# sch_AGV_Input.net
KiCad netlist of a schematic drawn in Altium Designer
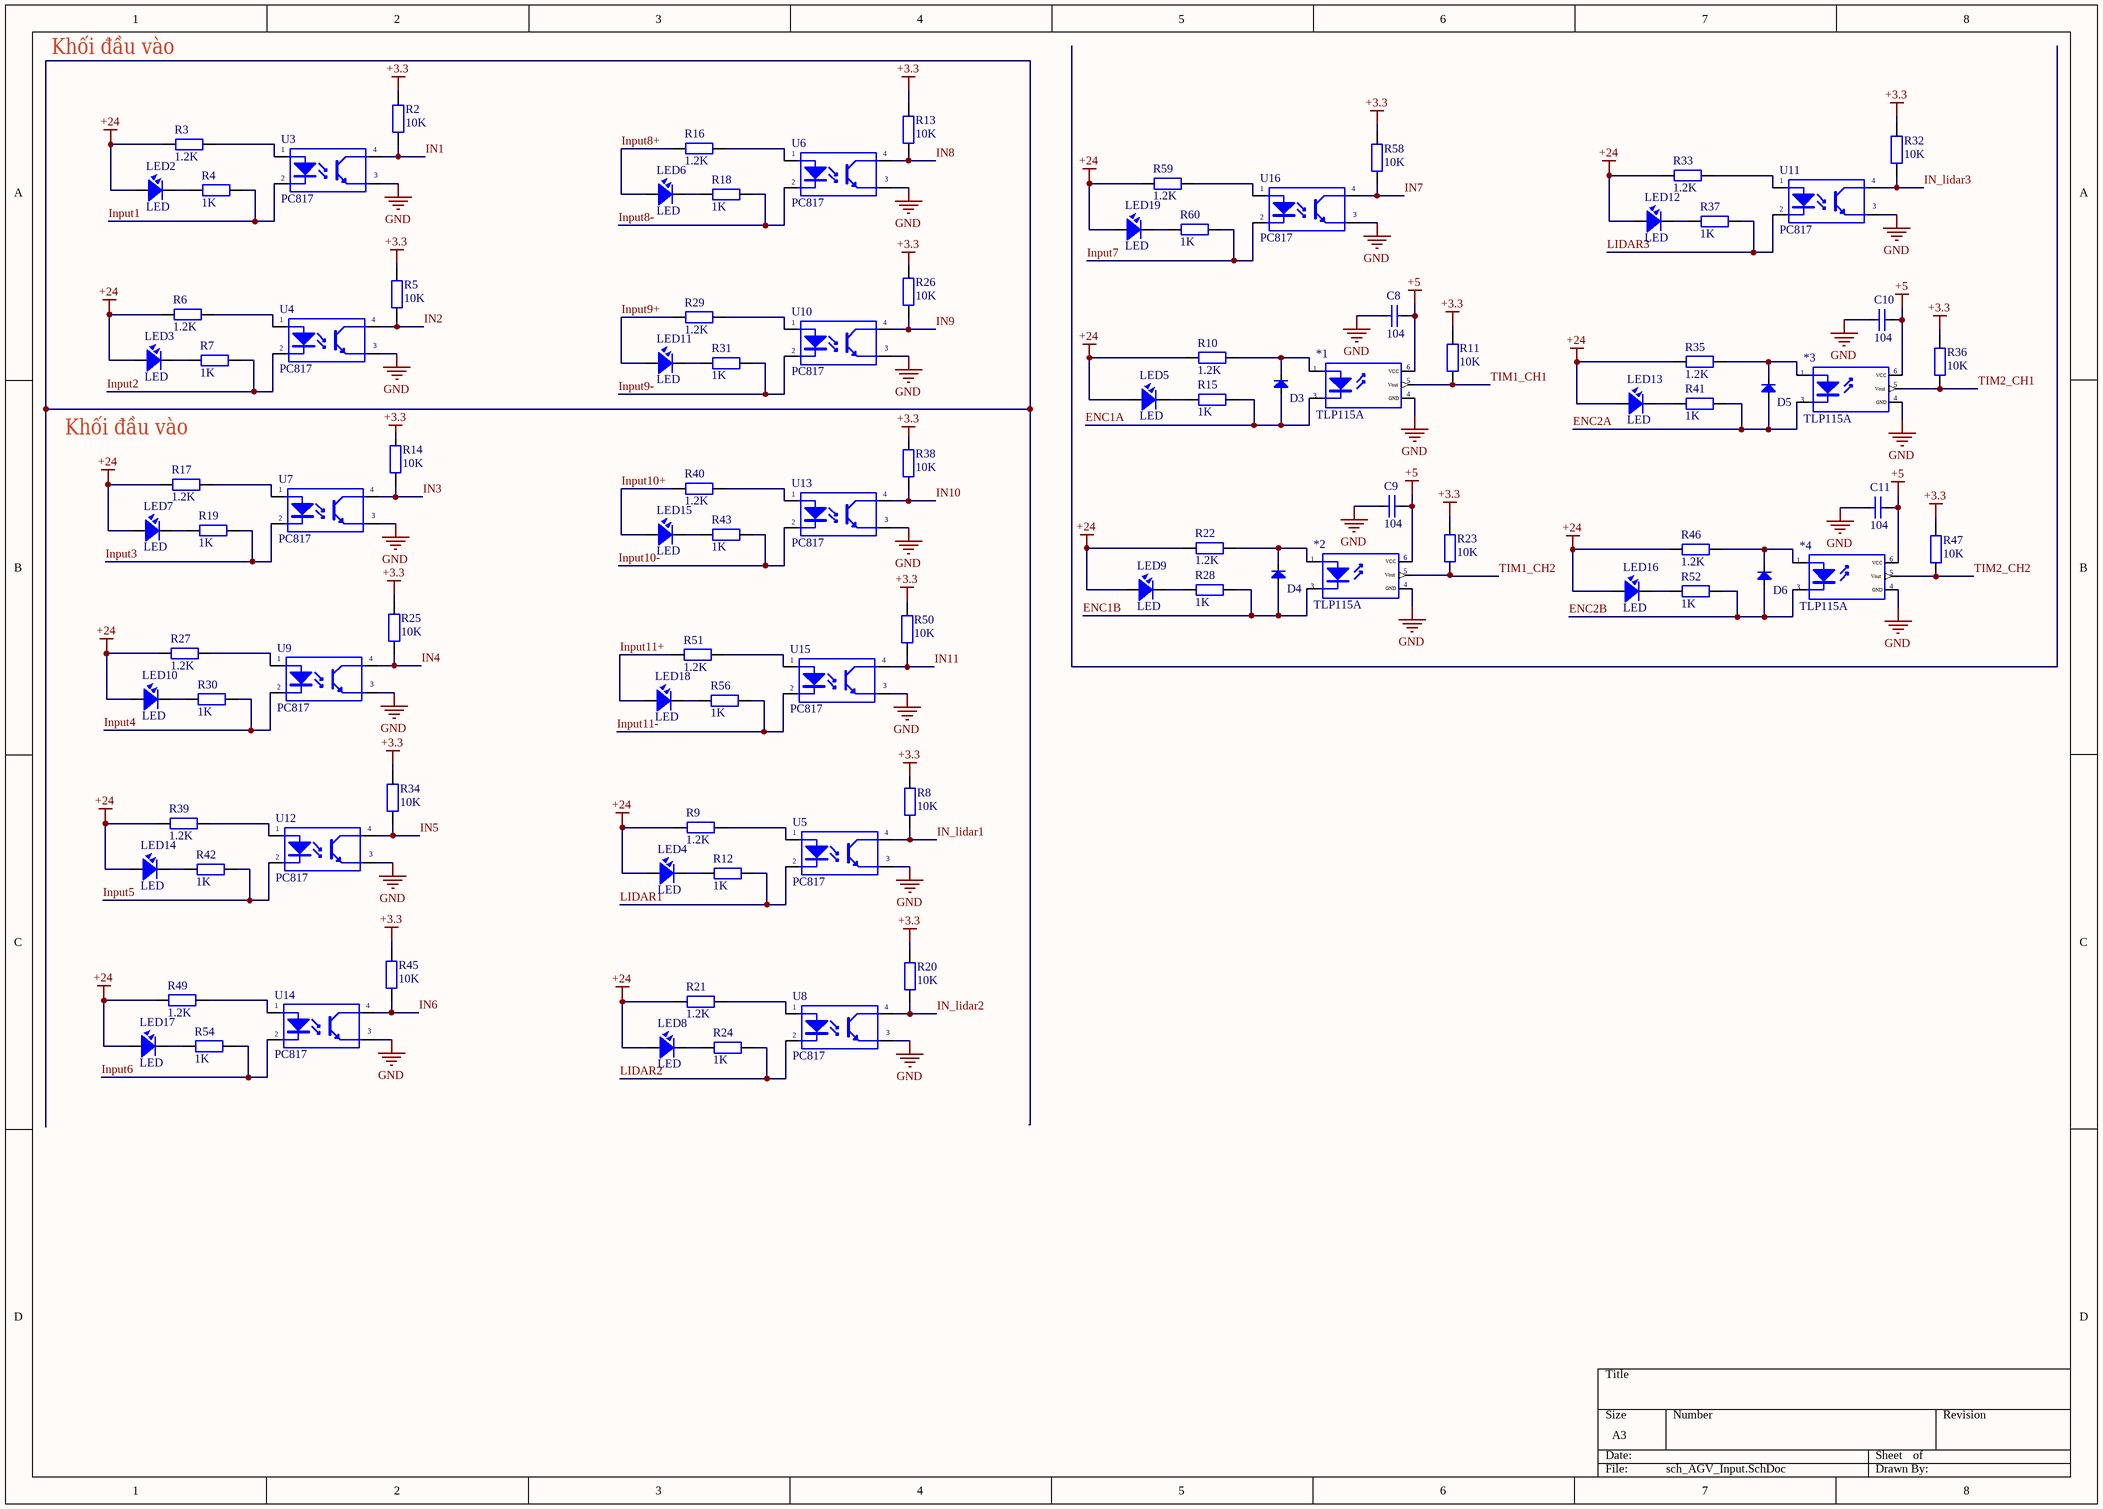
[diagram p0: sch_AGV_Input.SchDoc]

(export (version "E")
  (design (tool "Eeschema 10.0.6"))
  (components
    (comp (ref "*1")
      (value "TLP115A")
      (footprint "SOP5")
      (description "Photocouple")
      (libsource (lib "schelib_AGVcontrol") (part "TLP115A"))
    )
    (comp (ref "*2")
      (value "TLP115A")
      (footprint "SOP5")
      (description "Photocouple")
      (libsource (lib "schelib_AGVcontrol") (part "TLP115A"))
    )
    (comp (ref "*3")
      (value "TLP115A")
      (footprint "SOP5")
      (description "Photocouple")
      (libsource (lib "schelib_AGVcontrol") (part "TLP115A"))
    )
    (comp (ref "*4")
      (value "TLP115A")
      (footprint "SOP5")
      (description "Photocouple")
      (libsource (lib "schelib_AGVcontrol") (part "TLP115A"))
    )
    (comp (ref "C8")
      (value "104")
      (footprint "CAP_0805")
      (description "Capacitor")
      (fields (field (name "PUBLISHER") "Altium Limited"))
      (libsource (lib "schelib_AGVcontrol") (part "CapSMD"))
    )
    (comp (ref "C9")
      (value "104")
      (footprint "CAP_0805")
      (description "Capacitor")
      (fields (field (name "PUBLISHER") "Altium Limited"))
      (libsource (lib "schelib_AGVcontrol") (part "CapSMD"))
    )
    (comp (ref "C10")
      (value "104")
      (footprint "CAP_0805")
      (description "Capacitor")
      (fields (field (name "PUBLISHER") "Altium Limited"))
      (libsource (lib "schelib_AGVcontrol") (part "CapSMD"))
    )
    (comp (ref "C11")
      (value "104")
      (footprint "CAP_0805")
      (description "Capacitor")
      (fields (field (name "PUBLISHER") "Altium Limited"))
      (libsource (lib "schelib_AGVcontrol") (part "CapSMD"))
    )
    (comp (ref "D3")
      (value "Diode")
      (footprint "DIO-214AC(SMA)")
      (description "Default Diode")
      (fields (field (name "PUBLISHER") "Altium Limited"))
      (libsource (lib "schelib_AGVcontrol") (part "Diode"))
    )
    (comp (ref "D4")
      (value "Diode")
      (footprint "DIO-214AC(SMA)")
      (description "Default Diode")
      (fields (field (name "PUBLISHER") "Altium Limited"))
      (libsource (lib "schelib_AGVcontrol") (part "Diode"))
    )
    (comp (ref "D5")
      (value "Diode")
      (footprint "DIO-214AC(SMA)")
      (description "Default Diode")
      (fields (field (name "PUBLISHER") "Altium Limited"))
      (libsource (lib "schelib_AGVcontrol") (part "Diode"))
    )
    (comp (ref "D6")
      (value "Diode")
      (footprint "DIO-214AC(SMA)")
      (description "Default Diode")
      (fields (field (name "PUBLISHER") "Altium Limited"))
      (libsource (lib "schelib_AGVcontrol") (part "Diode"))
    )
    (comp (ref "LED2")
      (value "LED")
      (footprint "LED_BLUE_SMD_0805")
      (description "LED Single colour Green and Red")
      (libsource (lib "schelib_AGVcontrol") (part "LED"))
    )
    (comp (ref "LED3")
      (value "LED")
      (footprint "LED_BLUE_SMD_0805")
      (description "LED Single colour Green and Red")
      (libsource (lib "schelib_AGVcontrol") (part "LED"))
    )
    (comp (ref "LED4")
      (value "LED")
      (footprint "LED_BLUE_SMD_0805")
      (description "LED Single colour Green and Red")
      (libsource (lib "schelib_AGVcontrol") (part "LED"))
    )
    (comp (ref "LED5")
      (value "LED")
      (footprint "LED_BLUE_SMD_0805")
      (description "LED Single colour Green and Red")
      (libsource (lib "schelib_AGVcontrol") (part "LED"))
    )
    (comp (ref "LED6")
      (value "LED")
      (footprint "LED_BLUE_SMD_0805")
      (description "LED Single colour Green and Red")
      (libsource (lib "schelib_AGVcontrol") (part "LED"))
    )
    (comp (ref "LED7")
      (value "LED")
      (footprint "LED_BLUE_SMD_0805")
      (description "LED Single colour Green and Red")
      (libsource (lib "schelib_AGVcontrol") (part "LED"))
    )
    (comp (ref "LED8")
      (value "LED")
      (footprint "LED_BLUE_SMD_0805")
      (description "LED Single colour Green and Red")
      (libsource (lib "schelib_AGVcontrol") (part "LED"))
    )
    (comp (ref "LED9")
      (value "LED")
      (footprint "LED_BLUE_SMD_0805")
      (description "LED Single colour Green and Red")
      (libsource (lib "schelib_AGVcontrol") (part "LED"))
    )
    (comp (ref "LED10")
      (value "LED")
      (footprint "LED_BLUE_SMD_0805")
      (description "LED Single colour Green and Red")
      (libsource (lib "schelib_AGVcontrol") (part "LED"))
    )
    (comp (ref "LED11")
      (value "LED")
      (footprint "LED_BLUE_SMD_0805")
      (description "LED Single colour Green and Red")
      (libsource (lib "schelib_AGVcontrol") (part "LED"))
    )
    (comp (ref "LED12")
      (value "LED")
      (footprint "LED_BLUE_SMD_0805")
      (description "LED Single colour Green and Red")
      (libsource (lib "schelib_AGVcontrol") (part "LED"))
    )
    (comp (ref "LED13")
      (value "LED")
      (footprint "LED_BLUE_SMD_0805")
      (description "LED Single colour Green and Red")
      (libsource (lib "schelib_AGVcontrol") (part "LED"))
    )
    (comp (ref "LED14")
      (value "LED")
      (footprint "LED_BLUE_SMD_0805")
      (description "LED Single colour Green and Red")
      (libsource (lib "schelib_AGVcontrol") (part "LED"))
    )
    (comp (ref "LED15")
      (value "LED")
      (footprint "LED_BLUE_SMD_0805")
      (description "LED Single colour Green and Red")
      (libsource (lib "schelib_AGVcontrol") (part "LED"))
    )
    (comp (ref "LED16")
      (value "LED")
      (footprint "LED_BLUE_SMD_0805")
      (description "LED Single colour Green and Red")
      (libsource (lib "schelib_AGVcontrol") (part "LED"))
    )
    (comp (ref "LED17")
      (value "LED")
      (footprint "LED_BLUE_SMD_0805")
      (description "LED Single colour Green and Red")
      (libsource (lib "schelib_AGVcontrol") (part "LED"))
    )
    (comp (ref "LED18")
      (value "LED")
      (footprint "LED_BLUE_SMD_0805")
      (description "LED Single colour Green and Red")
      (libsource (lib "schelib_AGVcontrol") (part "LED"))
    )
    (comp (ref "LED19")
      (value "LED")
      (footprint "LED_BLUE_SMD_0805")
      (description "LED Single colour Green and Red")
      (libsource (lib "schelib_AGVcontrol") (part "LED"))
    )
    (comp (ref "R2")
      (value "10K")
      (footprint "RES_SMD_0805")
      (description "Resistor")
      (fields
        (field (name "MANUFACTURER") "Generic Components")
        (field (name "PUBLISHER") "Altium Hobart Technology Centre")
      )
      (libsource (lib "schelib_AGVcontrol") (part "Res"))
    )
    (comp (ref "R3")
      (value "1.2K")
      (footprint "RES_SMD_0805")
      (description "Resistor")
      (fields
        (field (name "MANUFACTURER") "Generic Components")
        (field (name "PUBLISHER") "Altium Hobart Technology Centre")
      )
      (libsource (lib "schelib_AGVcontrol") (part "Res"))
    )
    (comp (ref "R4")
      (value "1K")
      (footprint "RES_SMD_0805")
      (description "Resistor")
      (fields
        (field (name "MANUFACTURER") "Generic Components")
        (field (name "PUBLISHER") "Altium Hobart Technology Centre")
      )
      (libsource (lib "schelib_AGVcontrol") (part "Res"))
    )
    (comp (ref "R5")
      (value "10K")
      (footprint "RES_SMD_0805")
      (description "Resistor")
      (fields
        (field (name "MANUFACTURER") "Generic Components")
        (field (name "PUBLISHER") "Altium Hobart Technology Centre")
      )
      (libsource (lib "schelib_AGVcontrol") (part "Res"))
    )
    (comp (ref "R6")
      (value "1.2K")
      (footprint "RES_SMD_0805")
      (description "Resistor")
      (fields
        (field (name "MANUFACTURER") "Generic Components")
        (field (name "PUBLISHER") "Altium Hobart Technology Centre")
      )
      (libsource (lib "schelib_AGVcontrol") (part "Res"))
    )
    (comp (ref "R7")
      (value "1K")
      (footprint "RES_SMD_0805")
      (description "Resistor")
      (fields
        (field (name "MANUFACTURER") "Generic Components")
        (field (name "PUBLISHER") "Altium Hobart Technology Centre")
      )
      (libsource (lib "schelib_AGVcontrol") (part "Res"))
    )
    (comp (ref "R8")
      (value "10K")
      (footprint "RES_SMD_0805")
      (description "Resistor")
      (fields
        (field (name "MANUFACTURER") "Generic Components")
        (field (name "PUBLISHER") "Altium Hobart Technology Centre")
      )
      (libsource (lib "schelib_AGVcontrol") (part "Res"))
    )
    (comp (ref "R9")
      (value "1.2K")
      (footprint "RES_SMD_0805")
      (description "Resistor")
      (fields
        (field (name "MANUFACTURER") "Generic Components")
        (field (name "PUBLISHER") "Altium Hobart Technology Centre")
      )
      (libsource (lib "schelib_AGVcontrol") (part "Res"))
    )
    (comp (ref "R10")
      (value "1.2K")
      (footprint "RES_SMD_0805")
      (description "Resistor")
      (fields
        (field (name "MANUFACTURER") "Generic Components")
        (field (name "PUBLISHER") "Altium Hobart Technology Centre")
      )
      (libsource (lib "schelib_AGVcontrol") (part "Res"))
    )
    (comp (ref "R11")
      (value "10K")
      (footprint "RES_SMD_0805")
      (description "Resistor")
      (fields
        (field (name "MANUFACTURER") "Generic Components")
        (field (name "PUBLISHER") "Altium Hobart Technology Centre")
      )
      (libsource (lib "schelib_AGVcontrol") (part "Res"))
    )
    (comp (ref "R12")
      (value "1K")
      (footprint "RES_SMD_0805")
      (description "Resistor")
      (fields
        (field (name "MANUFACTURER") "Generic Components")
        (field (name "PUBLISHER") "Altium Hobart Technology Centre")
      )
      (libsource (lib "schelib_AGVcontrol") (part "Res"))
    )
    (comp (ref "R13")
      (value "10K")
      (footprint "RES_SMD_0805")
      (description "Resistor")
      (fields
        (field (name "MANUFACTURER") "Generic Components")
        (field (name "PUBLISHER") "Altium Hobart Technology Centre")
      )
      (libsource (lib "schelib_AGVcontrol") (part "Res"))
    )
    (comp (ref "R14")
      (value "10K")
      (footprint "RES_SMD_0805")
      (description "Resistor")
      (fields
        (field (name "MANUFACTURER") "Generic Components")
        (field (name "PUBLISHER") "Altium Hobart Technology Centre")
      )
      (libsource (lib "schelib_AGVcontrol") (part "Res"))
    )
    (comp (ref "R15")
      (value "1K")
      (footprint "RES_SMD_0805")
      (description "Resistor")
      (fields
        (field (name "MANUFACTURER") "Generic Components")
        (field (name "PUBLISHER") "Altium Hobart Technology Centre")
      )
      (libsource (lib "schelib_AGVcontrol") (part "Res"))
    )
    (comp (ref "R16")
      (value "1.2K")
      (footprint "RES_SMD_0805")
      (description "Resistor")
      (fields
        (field (name "MANUFACTURER") "Generic Components")
        (field (name "PUBLISHER") "Altium Hobart Technology Centre")
      )
      (libsource (lib "schelib_AGVcontrol") (part "Res"))
    )
    (comp (ref "R17")
      (value "1.2K")
      (footprint "RES_SMD_0805")
      (description "Resistor")
      (fields
        (field (name "MANUFACTURER") "Generic Components")
        (field (name "PUBLISHER") "Altium Hobart Technology Centre")
      )
      (libsource (lib "schelib_AGVcontrol") (part "Res"))
    )
    (comp (ref "R18")
      (value "1K")
      (footprint "RES_SMD_0805")
      (description "Resistor")
      (fields
        (field (name "MANUFACTURER") "Generic Components")
        (field (name "PUBLISHER") "Altium Hobart Technology Centre")
      )
      (libsource (lib "schelib_AGVcontrol") (part "Res"))
    )
    (comp (ref "R19")
      (value "1K")
      (footprint "RES_SMD_0805")
      (description "Resistor")
      (fields
        (field (name "MANUFACTURER") "Generic Components")
        (field (name "PUBLISHER") "Altium Hobart Technology Centre")
      )
      (libsource (lib "schelib_AGVcontrol") (part "Res"))
    )
    (comp (ref "R20")
      (value "10K")
      (footprint "RES_SMD_0805")
      (description "Resistor")
      (fields
        (field (name "MANUFACTURER") "Generic Components")
        (field (name "PUBLISHER") "Altium Hobart Technology Centre")
      )
      (libsource (lib "schelib_AGVcontrol") (part "Res"))
    )
    (comp (ref "R21")
      (value "1.2K")
      (footprint "RES_SMD_0805")
      (description "Resistor")
      (fields
        (field (name "MANUFACTURER") "Generic Components")
        (field (name "PUBLISHER") "Altium Hobart Technology Centre")
      )
      (libsource (lib "schelib_AGVcontrol") (part "Res"))
    )
    (comp (ref "R22")
      (value "1.2K")
      (footprint "RES_SMD_0805")
      (description "Resistor")
      (fields
        (field (name "MANUFACTURER") "Generic Components")
        (field (name "PUBLISHER") "Altium Hobart Technology Centre")
      )
      (libsource (lib "schelib_AGVcontrol") (part "Res"))
    )
    (comp (ref "R23")
      (value "10K")
      (footprint "RES_SMD_0805")
      (description "Resistor")
      (fields
        (field (name "MANUFACTURER") "Generic Components")
        (field (name "PUBLISHER") "Altium Hobart Technology Centre")
      )
      (libsource (lib "schelib_AGVcontrol") (part "Res"))
    )
    (comp (ref "R24")
      (value "1K")
      (footprint "RES_SMD_0805")
      (description "Resistor")
      (fields
        (field (name "MANUFACTURER") "Generic Components")
        (field (name "PUBLISHER") "Altium Hobart Technology Centre")
      )
      (libsource (lib "schelib_AGVcontrol") (part "Res"))
    )
    (comp (ref "R25")
      (value "10K")
      (footprint "RES_SMD_0805")
      (description "Resistor")
      (fields
        (field (name "MANUFACTURER") "Generic Components")
        (field (name "PUBLISHER") "Altium Hobart Technology Centre")
      )
      (libsource (lib "schelib_AGVcontrol") (part "Res"))
    )
    (comp (ref "R26")
      (value "10K")
      (footprint "RES_SMD_0805")
      (description "Resistor")
      (fields
        (field (name "MANUFACTURER") "Generic Components")
        (field (name "PUBLISHER") "Altium Hobart Technology Centre")
      )
      (libsource (lib "schelib_AGVcontrol") (part "Res"))
    )
    (comp (ref "R27")
      (value "1.2K")
      (footprint "RES_SMD_0805")
      (description "Resistor")
      (fields
        (field (name "MANUFACTURER") "Generic Components")
        (field (name "PUBLISHER") "Altium Hobart Technology Centre")
      )
      (libsource (lib "schelib_AGVcontrol") (part "Res"))
    )
    (comp (ref "R28")
      (value "1K")
      (footprint "RES_SMD_0805")
      (description "Resistor")
      (fields
        (field (name "MANUFACTURER") "Generic Components")
        (field (name "PUBLISHER") "Altium Hobart Technology Centre")
      )
      (libsource (lib "schelib_AGVcontrol") (part "Res"))
    )
    (comp (ref "R29")
      (value "1.2K")
      (footprint "RES_SMD_0805")
      (description "Resistor")
      (fields
        (field (name "MANUFACTURER") "Generic Components")
        (field (name "PUBLISHER") "Altium Hobart Technology Centre")
      )
      (libsource (lib "schelib_AGVcontrol") (part "Res"))
    )
    (comp (ref "R30")
      (value "1K")
      (footprint "RES_SMD_0805")
      (description "Resistor")
      (fields
        (field (name "MANUFACTURER") "Generic Components")
        (field (name "PUBLISHER") "Altium Hobart Technology Centre")
      )
      (libsource (lib "schelib_AGVcontrol") (part "Res"))
    )
    (comp (ref "R31")
      (value "1K")
      (footprint "RES_SMD_0805")
      (description "Resistor")
      (fields
        (field (name "MANUFACTURER") "Generic Components")
        (field (name "PUBLISHER") "Altium Hobart Technology Centre")
      )
      (libsource (lib "schelib_AGVcontrol") (part "Res"))
    )
    (comp (ref "R32")
      (value "10K")
      (footprint "RES_SMD_0805")
      (description "Resistor")
      (fields
        (field (name "MANUFACTURER") "Generic Components")
        (field (name "PUBLISHER") "Altium Hobart Technology Centre")
      )
      (libsource (lib "schelib_AGVcontrol") (part "Res"))
    )
    (comp (ref "R33")
      (value "1.2K")
      (footprint "RES_SMD_0805")
      (description "Resistor")
      (fields
        (field (name "MANUFACTURER") "Generic Components")
        (field (name "PUBLISHER") "Altium Hobart Technology Centre")
      )
      (libsource (lib "schelib_AGVcontrol") (part "Res"))
    )
    (comp (ref "R34")
      (value "10K")
      (footprint "RES_SMD_0805")
      (description "Resistor")
      (fields
        (field (name "MANUFACTURER") "Generic Components")
        (field (name "PUBLISHER") "Altium Hobart Technology Centre")
      )
      (libsource (lib "schelib_AGVcontrol") (part "Res"))
    )
    (comp (ref "R35")
      (value "1.2K")
      (footprint "RES_SMD_0805")
      (description "Resistor")
      (fields
        (field (name "MANUFACTURER") "Generic Components")
        (field (name "PUBLISHER") "Altium Hobart Technology Centre")
      )
      (libsource (lib "schelib_AGVcontrol") (part "Res"))
    )
    (comp (ref "R36")
      (value "10K")
      (footprint "RES_SMD_0805")
      (description "Resistor")
      (fields
        (field (name "MANUFACTURER") "Generic Components")
        (field (name "PUBLISHER") "Altium Hobart Technology Centre")
      )
      (libsource (lib "schelib_AGVcontrol") (part "Res"))
    )
    (comp (ref "R37")
      (value "1K")
      (footprint "RES_SMD_0805")
      (description "Resistor")
      (fields
        (field (name "MANUFACTURER") "Generic Components")
        (field (name "PUBLISHER") "Altium Hobart Technology Centre")
      )
      (libsource (lib "schelib_AGVcontrol") (part "Res"))
    )
    (comp (ref "R38")
      (value "10K")
      (footprint "RES_SMD_0805")
      (description "Resistor")
      (fields
        (field (name "MANUFACTURER") "Generic Components")
        (field (name "PUBLISHER") "Altium Hobart Technology Centre")
      )
      (libsource (lib "schelib_AGVcontrol") (part "Res"))
    )
    (comp (ref "R39")
      (value "1.2K")
      (footprint "RES_SMD_0805")
      (description "Resistor")
      (fields
        (field (name "MANUFACTURER") "Generic Components")
        (field (name "PUBLISHER") "Altium Hobart Technology Centre")
      )
      (libsource (lib "schelib_AGVcontrol") (part "Res"))
    )
    (comp (ref "R40")
      (value "1.2K")
      (footprint "RES_SMD_0805")
      (description "Resistor")
      (fields
        (field (name "MANUFACTURER") "Generic Components")
        (field (name "PUBLISHER") "Altium Hobart Technology Centre")
      )
      (libsource (lib "schelib_AGVcontrol") (part "Res"))
    )
    (comp (ref "R41")
      (value "1K")
      (footprint "RES_SMD_0805")
      (description "Resistor")
      (fields
        (field (name "MANUFACTURER") "Generic Components")
        (field (name "PUBLISHER") "Altium Hobart Technology Centre")
      )
      (libsource (lib "schelib_AGVcontrol") (part "Res"))
    )
    (comp (ref "R42")
      (value "1K")
      (footprint "RES_SMD_0805")
      (description "Resistor")
      (fields
        (field (name "MANUFACTURER") "Generic Components")
        (field (name "PUBLISHER") "Altium Hobart Technology Centre")
      )
      (libsource (lib "schelib_AGVcontrol") (part "Res"))
    )
    (comp (ref "R43")
      (value "1K")
      (footprint "RES_SMD_0805")
      (description "Resistor")
      (fields
        (field (name "MANUFACTURER") "Generic Components")
        (field (name "PUBLISHER") "Altium Hobart Technology Centre")
      )
      (libsource (lib "schelib_AGVcontrol") (part "Res"))
    )
    (comp (ref "R45")
      (value "10K")
      (footprint "RES_SMD_0805")
      (description "Resistor")
      (fields
        (field (name "MANUFACTURER") "Generic Components")
        (field (name "PUBLISHER") "Altium Hobart Technology Centre")
      )
      (libsource (lib "schelib_AGVcontrol") (part "Res"))
    )
    (comp (ref "R46")
      (value "1.2K")
      (footprint "RES_SMD_0805")
      (description "Resistor")
      (fields
        (field (name "MANUFACTURER") "Generic Components")
        (field (name "PUBLISHER") "Altium Hobart Technology Centre")
      )
      (libsource (lib "schelib_AGVcontrol") (part "Res"))
    )
    (comp (ref "R47")
      (value "10K")
      (footprint "RES_SMD_0805")
      (description "Resistor")
      (fields
        (field (name "MANUFACTURER") "Generic Components")
        (field (name "PUBLISHER") "Altium Hobart Technology Centre")
      )
      (libsource (lib "schelib_AGVcontrol") (part "Res"))
    )
    (comp (ref "R49")
      (value "1.2K")
      (footprint "RES_SMD_0805")
      (description "Resistor")
      (fields
        (field (name "MANUFACTURER") "Generic Components")
        (field (name "PUBLISHER") "Altium Hobart Technology Centre")
      )
      (libsource (lib "schelib_AGVcontrol") (part "Res"))
    )
    (comp (ref "R50")
      (value "10K")
      (footprint "RES_SMD_0805")
      (description "Resistor")
      (fields
        (field (name "MANUFACTURER") "Generic Components")
        (field (name "PUBLISHER") "Altium Hobart Technology Centre")
      )
      (libsource (lib "schelib_AGVcontrol") (part "Res"))
    )
    (comp (ref "R51")
      (value "1.2K")
      (footprint "RES_SMD_0805")
      (description "Resistor")
      (fields
        (field (name "MANUFACTURER") "Generic Components")
        (field (name "PUBLISHER") "Altium Hobart Technology Centre")
      )
      (libsource (lib "schelib_AGVcontrol") (part "Res"))
    )
    (comp (ref "R52")
      (value "1K")
      (footprint "RES_SMD_0805")
      (description "Resistor")
      (fields
        (field (name "MANUFACTURER") "Generic Components")
        (field (name "PUBLISHER") "Altium Hobart Technology Centre")
      )
      (libsource (lib "schelib_AGVcontrol") (part "Res"))
    )
    (comp (ref "R54")
      (value "1K")
      (footprint "RES_SMD_0805")
      (description "Resistor")
      (fields
        (field (name "MANUFACTURER") "Generic Components")
        (field (name "PUBLISHER") "Altium Hobart Technology Centre")
      )
      (libsource (lib "schelib_AGVcontrol") (part "Res"))
    )
    (comp (ref "R56")
      (value "1K")
      (footprint "RES_SMD_0805")
      (description "Resistor")
      (fields
        (field (name "MANUFACTURER") "Generic Components")
        (field (name "PUBLISHER") "Altium Hobart Technology Centre")
      )
      (libsource (lib "schelib_AGVcontrol") (part "Res"))
    )
    (comp (ref "R58")
      (value "10K")
      (footprint "RES_SMD_0805")
      (description "Resistor")
      (fields
        (field (name "MANUFACTURER") "Generic Components")
        (field (name "PUBLISHER") "Altium Hobart Technology Centre")
      )
      (libsource (lib "schelib_AGVcontrol") (part "Res"))
    )
    (comp (ref "R59")
      (value "1.2K")
      (footprint "RES_SMD_0805")
      (description "Resistor")
      (fields
        (field (name "MANUFACTURER") "Generic Components")
        (field (name "PUBLISHER") "Altium Hobart Technology Centre")
      )
      (libsource (lib "schelib_AGVcontrol") (part "Res"))
    )
    (comp (ref "R60")
      (value "1K")
      (footprint "RES_SMD_0805")
      (description "Resistor")
      (fields
        (field (name "MANUFACTURER") "Generic Components")
        (field (name "PUBLISHER") "Altium Hobart Technology Centre")
      )
      (libsource (lib "schelib_AGVcontrol") (part "Res"))
    )
    (comp (ref "U3")
      (value "PC817")
      (footprint "DIP4/W0.3")
      (description "Single Opto")
      (libsource (lib "schelib_AGVcontrol") (part "PC817"))
    )
    (comp (ref "U4")
      (value "PC817")
      (footprint "DIP4/W0.3")
      (description "Single Opto")
      (libsource (lib "schelib_AGVcontrol") (part "PC817"))
    )
    (comp (ref "U5")
      (value "PC817")
      (footprint "DIP4/W0.3")
      (description "Single Opto")
      (libsource (lib "schelib_AGVcontrol") (part "PC817"))
    )
    (comp (ref "U6")
      (value "PC817")
      (footprint "DIP4/W0.3")
      (description "Single Opto")
      (libsource (lib "schelib_AGVcontrol") (part "PC817"))
    )
    (comp (ref "U7")
      (value "PC817")
      (footprint "DIP4/W0.3")
      (description "Single Opto")
      (libsource (lib "schelib_AGVcontrol") (part "PC817"))
    )
    (comp (ref "U8")
      (value "PC817")
      (footprint "DIP4/W0.3")
      (description "Single Opto")
      (libsource (lib "schelib_AGVcontrol") (part "PC817"))
    )
    (comp (ref "U9")
      (value "PC817")
      (footprint "DIP4/W0.3")
      (description "Single Opto")
      (libsource (lib "schelib_AGVcontrol") (part "PC817"))
    )
    (comp (ref "U10")
      (value "PC817")
      (footprint "DIP4/W0.3")
      (description "Single Opto")
      (libsource (lib "schelib_AGVcontrol") (part "PC817"))
    )
    (comp (ref "U11")
      (value "PC817")
      (footprint "DIP4/W0.3")
      (description "Single Opto")
      (libsource (lib "schelib_AGVcontrol") (part "PC817"))
    )
    (comp (ref "U12")
      (value "PC817")
      (footprint "DIP4/W0.3")
      (description "Single Opto")
      (libsource (lib "schelib_AGVcontrol") (part "PC817"))
    )
    (comp (ref "U13")
      (value "PC817")
      (footprint "DIP4/W0.3")
      (description "Single Opto")
      (libsource (lib "schelib_AGVcontrol") (part "PC817"))
    )
    (comp (ref "U14")
      (value "PC817")
      (footprint "DIP4/W0.3")
      (description "Single Opto")
      (libsource (lib "schelib_AGVcontrol") (part "PC817"))
    )
    (comp (ref "U15")
      (value "PC817")
      (footprint "DIP4/W0.3")
      (description "Single Opto")
      (libsource (lib "schelib_AGVcontrol") (part "PC817"))
    )
    (comp (ref "U16")
      (value "PC817")
      (footprint "DIP4/W0.3")
      (description "Single Opto")
      (libsource (lib "schelib_AGVcontrol") (part "PC817"))
    )
  )
  (nets
    (net (code "1") (name "+3.3") (class "Default")
      (node (ref "R11") (pin "1") (pinfunction "1_1") (pintype "passive"))
      (node (ref "R13") (pin "1") (pinfunction "1_1") (pintype "passive"))
      (node (ref "R14") (pin "1") (pinfunction "1_1") (pintype "passive"))
      (node (ref "R2") (pin "1") (pinfunction "1_1") (pintype "passive"))
      (node (ref "R20") (pin "1") (pinfunction "1_1") (pintype "passive"))
      (node (ref "R23") (pin "1") (pinfunction "1_1") (pintype "passive"))
      (node (ref "R25") (pin "1") (pinfunction "1_1") (pintype "passive"))
      (node (ref "R26") (pin "1") (pinfunction "1_1") (pintype "passive"))
      (node (ref "R32") (pin "1") (pinfunction "1_1") (pintype "passive"))
      (node (ref "R34") (pin "1") (pinfunction "1_1") (pintype "passive"))
      (node (ref "R36") (pin "1") (pinfunction "1_1") (pintype "passive"))
      (node (ref "R38") (pin "1") (pinfunction "1_1") (pintype "passive"))
      (node (ref "R45") (pin "1") (pinfunction "1_1") (pintype "passive"))
      (node (ref "R47") (pin "1") (pinfunction "1_1") (pintype "passive"))
      (node (ref "R5") (pin "1") (pinfunction "1_1") (pintype "passive"))
      (node (ref "R50") (pin "1") (pinfunction "1_1") (pintype "passive"))
      (node (ref "R58") (pin "1") (pinfunction "1_1") (pintype "passive"))
      (node (ref "R8") (pin "1") (pinfunction "1_1") (pintype "passive"))
    )
    (net (code "2") (name "+5") (class "Default")
      (node (ref "*1") (pin "6") (pinfunction "C_6") (pintype "power_in"))
      (node (ref "*2") (pin "6") (pinfunction "C_6") (pintype "power_in"))
      (node (ref "*3") (pin "6") (pinfunction "C_6") (pintype "power_in"))
      (node (ref "*4") (pin "6") (pinfunction "C_6") (pintype "power_in"))
      (node (ref "C10") (pin "2") (pinfunction "2_2") (pintype "passive"))
      (node (ref "C11") (pin "2") (pinfunction "2_2") (pintype "passive"))
      (node (ref "C8") (pin "2") (pinfunction "2_2") (pintype "passive"))
      (node (ref "C9") (pin "2") (pinfunction "2_2") (pintype "passive"))
    )
    (net (code "3") (name "+24") (class "Default")
      (node (ref "LED10") (pin "1") (pinfunction "1_1") (pintype "passive"))
      (node (ref "LED12") (pin "1") (pinfunction "1_1") (pintype "passive"))
      (node (ref "LED13") (pin "1") (pinfunction "1_1") (pintype "passive"))
      (node (ref "LED14") (pin "1") (pinfunction "1_1") (pintype "passive"))
      (node (ref "LED16") (pin "1") (pinfunction "1_1") (pintype "passive"))
      (node (ref "LED17") (pin "1") (pinfunction "1_1") (pintype "passive"))
      (node (ref "LED19") (pin "1") (pinfunction "1_1") (pintype "passive"))
      (node (ref "LED2") (pin "1") (pinfunction "1_1") (pintype "passive"))
      (node (ref "LED3") (pin "1") (pinfunction "1_1") (pintype "passive"))
      (node (ref "LED4") (pin "1") (pinfunction "1_1") (pintype "passive"))
      (node (ref "LED5") (pin "1") (pinfunction "1_1") (pintype "passive"))
      (node (ref "LED7") (pin "1") (pinfunction "1_1") (pintype "passive"))
      (node (ref "LED8") (pin "1") (pinfunction "1_1") (pintype "passive"))
      (node (ref "LED9") (pin "1") (pinfunction "1_1") (pintype "passive"))
      (node (ref "R10") (pin "1") (pinfunction "1_1") (pintype "passive"))
      (node (ref "R17") (pin "1") (pinfunction "1_1") (pintype "passive"))
      (node (ref "R21") (pin "1") (pinfunction "1_1") (pintype "passive"))
      (node (ref "R22") (pin "1") (pinfunction "1_1") (pintype "passive"))
      (node (ref "R27") (pin "1") (pinfunction "1_1") (pintype "passive"))
      (node (ref "R3") (pin "1") (pinfunction "1_1") (pintype "passive"))
      (node (ref "R33") (pin "1") (pinfunction "1_1") (pintype "passive"))
      (node (ref "R35") (pin "1") (pinfunction "1_1") (pintype "passive"))
      (node (ref "R39") (pin "1") (pinfunction "1_1") (pintype "passive"))
      (node (ref "R46") (pin "1") (pinfunction "1_1") (pintype "passive"))
      (node (ref "R49") (pin "1") (pinfunction "1_1") (pintype "passive"))
      (node (ref "R59") (pin "1") (pinfunction "1_1") (pintype "passive"))
      (node (ref "R6") (pin "1") (pinfunction "1_1") (pintype "passive"))
      (node (ref "R9") (pin "1") (pinfunction "1_1") (pintype "passive"))
    )
    (net (code "4") (name "/ENC1A") (class "Default")
      (node (ref "*1") (pin "3") (pinfunction "K_3") (pintype "passive"))
      (node (ref "D3") (pin "1") (pinfunction "A_1") (pintype "passive"))
      (node (ref "R15") (pin "2") (pinfunction "2_2") (pintype "passive"))
    )
    (net (code "5") (name "/ENC1B") (class "Default")
      (node (ref "*2") (pin "3") (pinfunction "K_3") (pintype "passive"))
      (node (ref "D4") (pin "1") (pinfunction "A_1") (pintype "passive"))
      (node (ref "R28") (pin "2") (pinfunction "2_2") (pintype "passive"))
    )
    (net (code "6") (name "/ENC2A") (class "Default")
      (node (ref "*3") (pin "3") (pinfunction "K_3") (pintype "passive"))
      (node (ref "D5") (pin "1") (pinfunction "A_1") (pintype "passive"))
      (node (ref "R41") (pin "2") (pinfunction "2_2") (pintype "passive"))
    )
    (net (code "7") (name "/ENC2B") (class "Default")
      (node (ref "*4") (pin "3") (pinfunction "K_3") (pintype "passive"))
      (node (ref "D6") (pin "1") (pinfunction "A_1") (pintype "passive"))
      (node (ref "R52") (pin "2") (pinfunction "2_2") (pintype "passive"))
    )
    (net (code "8") (name "/IN1") (class "Default")
      (node (ref "R2") (pin "2") (pinfunction "2_2") (pintype "passive"))
      (node (ref "U3") (pin "4") (pinfunction "C_4") (pintype "passive"))
    )
    (net (code "9") (name "/IN2") (class "Default")
      (node (ref "R5") (pin "2") (pinfunction "2_2") (pintype "passive"))
      (node (ref "U4") (pin "4") (pinfunction "C_4") (pintype "passive"))
    )
    (net (code "10") (name "/IN3") (class "Default")
      (node (ref "R14") (pin "2") (pinfunction "2_2") (pintype "passive"))
      (node (ref "U7") (pin "4") (pinfunction "C_4") (pintype "passive"))
    )
    (net (code "11") (name "/IN4") (class "Default")
      (node (ref "R25") (pin "2") (pinfunction "2_2") (pintype "passive"))
      (node (ref "U9") (pin "4") (pinfunction "C_4") (pintype "passive"))
    )
    (net (code "12") (name "/IN5") (class "Default")
      (node (ref "R34") (pin "2") (pinfunction "2_2") (pintype "passive"))
      (node (ref "U12") (pin "4") (pinfunction "C_4") (pintype "passive"))
    )
    (net (code "13") (name "/IN6") (class "Default")
      (node (ref "R45") (pin "2") (pinfunction "2_2") (pintype "passive"))
      (node (ref "U14") (pin "4") (pinfunction "C_4") (pintype "passive"))
    )
    (net (code "14") (name "/IN7") (class "Default")
      (node (ref "R58") (pin "2") (pinfunction "2_2") (pintype "passive"))
      (node (ref "U16") (pin "4") (pinfunction "C_4") (pintype "passive"))
    )
    (net (code "15") (name "/IN8") (class "Default")
      (node (ref "R13") (pin "2") (pinfunction "2_2") (pintype "passive"))
      (node (ref "U6") (pin "4") (pinfunction "C_4") (pintype "passive"))
    )
    (net (code "16") (name "/IN9") (class "Default")
      (node (ref "R26") (pin "2") (pinfunction "2_2") (pintype "passive"))
      (node (ref "U10") (pin "4") (pinfunction "C_4") (pintype "passive"))
    )
    (net (code "17") (name "/IN10") (class "Default")
      (node (ref "R38") (pin "2") (pinfunction "2_2") (pintype "passive"))
      (node (ref "U13") (pin "4") (pinfunction "C_4") (pintype "passive"))
    )
    (net (code "18") (name "/IN11") (class "Default")
      (node (ref "R50") (pin "2") (pinfunction "2_2") (pintype "passive"))
      (node (ref "U15") (pin "4") (pinfunction "C_4") (pintype "passive"))
    )
    (net (code "19") (name "/IN_lidar1") (class "Default")
      (node (ref "R8") (pin "2") (pinfunction "2_2") (pintype "passive"))
      (node (ref "U5") (pin "4") (pinfunction "C_4") (pintype "passive"))
    )
    (net (code "20") (name "/IN_lidar2") (class "Default")
      (node (ref "R20") (pin "2") (pinfunction "2_2") (pintype "passive"))
      (node (ref "U8") (pin "4") (pinfunction "C_4") (pintype "passive"))
    )
    (net (code "21") (name "/IN_lidar3") (class "Default")
      (node (ref "R32") (pin "2") (pinfunction "2_2") (pintype "passive"))
      (node (ref "U11") (pin "4") (pinfunction "C_4") (pintype "passive"))
    )
    (net (code "22") (name "/Input1") (class "Default")
      (node (ref "R4") (pin "2") (pinfunction "2_2") (pintype "passive"))
      (node (ref "U3") (pin "2") (pinfunction "K_2") (pintype "passive"))
    )
    (net (code "23") (name "/Input2") (class "Default")
      (node (ref "R7") (pin "2") (pinfunction "2_2") (pintype "passive"))
      (node (ref "U4") (pin "2") (pinfunction "K_2") (pintype "passive"))
    )
    (net (code "24") (name "/Input3") (class "Default")
      (node (ref "R19") (pin "2") (pinfunction "2_2") (pintype "passive"))
      (node (ref "U7") (pin "2") (pinfunction "K_2") (pintype "passive"))
    )
    (net (code "25") (name "/Input4") (class "Default")
      (node (ref "R30") (pin "2") (pinfunction "2_2") (pintype "passive"))
      (node (ref "U9") (pin "2") (pinfunction "K_2") (pintype "passive"))
    )
    (net (code "26") (name "/Input5") (class "Default")
      (node (ref "R42") (pin "2") (pinfunction "2_2") (pintype "passive"))
      (node (ref "U12") (pin "2") (pinfunction "K_2") (pintype "passive"))
    )
    (net (code "27") (name "/Input6") (class "Default")
      (node (ref "R54") (pin "2") (pinfunction "2_2") (pintype "passive"))
      (node (ref "U14") (pin "2") (pinfunction "K_2") (pintype "passive"))
    )
    (net (code "28") (name "/Input7") (class "Default")
      (node (ref "R60") (pin "2") (pinfunction "2_2") (pintype "passive"))
      (node (ref "U16") (pin "2") (pinfunction "K_2") (pintype "passive"))
    )
    (net (code "29") (name "/Input8+") (class "Default")
      (node (ref "LED6") (pin "1") (pinfunction "1_1") (pintype "passive"))
      (node (ref "R16") (pin "1") (pinfunction "1_1") (pintype "passive"))
    )
    (net (code "30") (name "/Input8-") (class "Default")
      (node (ref "R18") (pin "2") (pinfunction "2_2") (pintype "passive"))
      (node (ref "U6") (pin "2") (pinfunction "K_2") (pintype "passive"))
    )
    (net (code "31") (name "/Input9+") (class "Default")
      (node (ref "LED11") (pin "1") (pinfunction "1_1") (pintype "passive"))
      (node (ref "R29") (pin "1") (pinfunction "1_1") (pintype "passive"))
    )
    (net (code "32") (name "/Input9-") (class "Default")
      (node (ref "R31") (pin "2") (pinfunction "2_2") (pintype "passive"))
      (node (ref "U10") (pin "2") (pinfunction "K_2") (pintype "passive"))
    )
    (net (code "33") (name "/Input10+") (class "Default")
      (node (ref "LED15") (pin "1") (pinfunction "1_1") (pintype "passive"))
      (node (ref "R40") (pin "1") (pinfunction "1_1") (pintype "passive"))
    )
    (net (code "34") (name "/Input10-") (class "Default")
      (node (ref "R43") (pin "2") (pinfunction "2_2") (pintype "passive"))
      (node (ref "U13") (pin "2") (pinfunction "K_2") (pintype "passive"))
    )
    (net (code "35") (name "/Input11+") (class "Default")
      (node (ref "LED18") (pin "1") (pinfunction "1_1") (pintype "passive"))
      (node (ref "R51") (pin "1") (pinfunction "1_1") (pintype "passive"))
    )
    (net (code "36") (name "/Input11-") (class "Default")
      (node (ref "R56") (pin "2") (pinfunction "2_2") (pintype "passive"))
      (node (ref "U15") (pin "2") (pinfunction "K_2") (pintype "passive"))
    )
    (net (code "37") (name "/LIDAR1") (class "Default")
      (node (ref "R12") (pin "2") (pinfunction "2_2") (pintype "passive"))
      (node (ref "U5") (pin "2") (pinfunction "K_2") (pintype "passive"))
    )
    (net (code "38") (name "/LIDAR2") (class "Default")
      (node (ref "R24") (pin "2") (pinfunction "2_2") (pintype "passive"))
      (node (ref "U8") (pin "2") (pinfunction "K_2") (pintype "passive"))
    )
    (net (code "39") (name "/LIDAR3") (class "Default")
      (node (ref "R37") (pin "2") (pinfunction "2_2") (pintype "passive"))
      (node (ref "U11") (pin "2") (pinfunction "K_2") (pintype "passive"))
    )
    (net (code "40") (name "/TIM1_CH1") (class "Default")
      (node (ref "*1") (pin "5") (pinfunction "Out_5") (pintype "output"))
      (node (ref "R11") (pin "2") (pinfunction "2_2") (pintype "passive"))
    )
    (net (code "41") (name "/TIM1_CH2") (class "Default")
      (node (ref "*2") (pin "5") (pinfunction "Out_5") (pintype "output"))
      (node (ref "R23") (pin "2") (pinfunction "2_2") (pintype "passive"))
    )
    (net (code "42") (name "/TIM2_CH1") (class "Default")
      (node (ref "*3") (pin "5") (pinfunction "Out_5") (pintype "output"))
      (node (ref "R36") (pin "2") (pinfunction "2_2") (pintype "passive"))
    )
    (net (code "43") (name "/TIM2_CH2") (class "Default")
      (node (ref "*4") (pin "5") (pinfunction "Out_5") (pintype "output"))
      (node (ref "R47") (pin "2") (pinfunction "2_2") (pintype "passive"))
    )
    (net (code "44") (name "GND") (class "Default")
      (node (ref "*1") (pin "4") (pinfunction "E_4") (pintype "power_in"))
      (node (ref "*2") (pin "4") (pinfunction "E_4") (pintype "power_in"))
      (node (ref "*3") (pin "4") (pinfunction "E_4") (pintype "power_in"))
      (node (ref "*4") (pin "4") (pinfunction "E_4") (pintype "power_in"))
      (node (ref "C10") (pin "1") (pinfunction "1_1") (pintype "passive"))
      (node (ref "C11") (pin "1") (pinfunction "1_1") (pintype "passive"))
      (node (ref "C8") (pin "1") (pinfunction "1_1") (pintype "passive"))
      (node (ref "C9") (pin "1") (pinfunction "1_1") (pintype "passive"))
      (node (ref "U10") (pin "3") (pinfunction "E_3") (pintype "passive"))
      (node (ref "U11") (pin "3") (pinfunction "E_3") (pintype "passive"))
      (node (ref "U12") (pin "3") (pinfunction "E_3") (pintype "passive"))
      (node (ref "U13") (pin "3") (pinfunction "E_3") (pintype "passive"))
      (node (ref "U14") (pin "3") (pinfunction "E_3") (pintype "passive"))
      (node (ref "U15") (pin "3") (pinfunction "E_3") (pintype "passive"))
      (node (ref "U16") (pin "3") (pinfunction "E_3") (pintype "passive"))
      (node (ref "U3") (pin "3") (pinfunction "E_3") (pintype "passive"))
      (node (ref "U4") (pin "3") (pinfunction "E_3") (pintype "passive"))
      (node (ref "U5") (pin "3") (pinfunction "E_3") (pintype "passive"))
      (node (ref "U6") (pin "3") (pinfunction "E_3") (pintype "passive"))
      (node (ref "U7") (pin "3") (pinfunction "E_3") (pintype "passive"))
      (node (ref "U8") (pin "3") (pinfunction "E_3") (pintype "passive"))
      (node (ref "U9") (pin "3") (pinfunction "E_3") (pintype "passive"))
    )
    (net (code "45") (name "Net-(*1-A)") (class "Default")
      (node (ref "*1") (pin "1") (pinfunction "A_1") (pintype "passive"))
      (node (ref "D3") (pin "2") (pinfunction "K_2") (pintype "passive"))
      (node (ref "R10") (pin "2") (pinfunction "2_2") (pintype "passive"))
    )
    (net (code "46") (name "Net-(*2-A)") (class "Default")
      (node (ref "*2") (pin "1") (pinfunction "A_1") (pintype "passive"))
      (node (ref "D4") (pin "2") (pinfunction "K_2") (pintype "passive"))
      (node (ref "R22") (pin "2") (pinfunction "2_2") (pintype "passive"))
    )
    (net (code "47") (name "Net-(*3-A)") (class "Default")
      (node (ref "*3") (pin "1") (pinfunction "A_1") (pintype "passive"))
      (node (ref "D5") (pin "2") (pinfunction "K_2") (pintype "passive"))
      (node (ref "R35") (pin "2") (pinfunction "2_2") (pintype "passive"))
    )
    (net (code "48") (name "Net-(*4-A)") (class "Default")
      (node (ref "*4") (pin "1") (pinfunction "A_1") (pintype "passive"))
      (node (ref "D6") (pin "2") (pinfunction "K_2") (pintype "passive"))
      (node (ref "R46") (pin "2") (pinfunction "2_2") (pintype "passive"))
    )
    (net (code "49") (name "Net-(LED2-Pad2)") (class "Default")
      (node (ref "LED2") (pin "2") (pinfunction "2_2") (pintype "passive"))
      (node (ref "R4") (pin "1") (pinfunction "1_1") (pintype "passive"))
    )
    (net (code "50") (name "Net-(LED3-Pad2)") (class "Default")
      (node (ref "LED3") (pin "2") (pinfunction "2_2") (pintype "passive"))
      (node (ref "R7") (pin "1") (pinfunction "1_1") (pintype "passive"))
    )
    (net (code "51") (name "Net-(LED4-Pad2)") (class "Default")
      (node (ref "LED4") (pin "2") (pinfunction "2_2") (pintype "passive"))
      (node (ref "R12") (pin "1") (pinfunction "1_1") (pintype "passive"))
    )
    (net (code "52") (name "Net-(LED5-Pad2)") (class "Default")
      (node (ref "LED5") (pin "2") (pinfunction "2_2") (pintype "passive"))
      (node (ref "R15") (pin "1") (pinfunction "1_1") (pintype "passive"))
    )
    (net (code "53") (name "Net-(LED6-Pad2)") (class "Default")
      (node (ref "LED6") (pin "2") (pinfunction "2_2") (pintype "passive"))
      (node (ref "R18") (pin "1") (pinfunction "1_1") (pintype "passive"))
    )
    (net (code "54") (name "Net-(LED7-Pad2)") (class "Default")
      (node (ref "LED7") (pin "2") (pinfunction "2_2") (pintype "passive"))
      (node (ref "R19") (pin "1") (pinfunction "1_1") (pintype "passive"))
    )
    (net (code "55") (name "Net-(LED8-Pad2)") (class "Default")
      (node (ref "LED8") (pin "2") (pinfunction "2_2") (pintype "passive"))
      (node (ref "R24") (pin "1") (pinfunction "1_1") (pintype "passive"))
    )
    (net (code "56") (name "Net-(LED9-Pad2)") (class "Default")
      (node (ref "LED9") (pin "2") (pinfunction "2_2") (pintype "passive"))
      (node (ref "R28") (pin "1") (pinfunction "1_1") (pintype "passive"))
    )
    (net (code "57") (name "Net-(LED10-Pad2)") (class "Default")
      (node (ref "LED10") (pin "2") (pinfunction "2_2") (pintype "passive"))
      (node (ref "R30") (pin "1") (pinfunction "1_1") (pintype "passive"))
    )
    (net (code "58") (name "Net-(LED11-Pad2)") (class "Default")
      (node (ref "LED11") (pin "2") (pinfunction "2_2") (pintype "passive"))
      (node (ref "R31") (pin "1") (pinfunction "1_1") (pintype "passive"))
    )
    (net (code "59") (name "Net-(LED12-Pad2)") (class "Default")
      (node (ref "LED12") (pin "2") (pinfunction "2_2") (pintype "passive"))
      (node (ref "R37") (pin "1") (pinfunction "1_1") (pintype "passive"))
    )
    (net (code "60") (name "Net-(LED13-Pad2)") (class "Default")
      (node (ref "LED13") (pin "2") (pinfunction "2_2") (pintype "passive"))
      (node (ref "R41") (pin "1") (pinfunction "1_1") (pintype "passive"))
    )
    (net (code "61") (name "Net-(LED14-Pad2)") (class "Default")
      (node (ref "LED14") (pin "2") (pinfunction "2_2") (pintype "passive"))
      (node (ref "R42") (pin "1") (pinfunction "1_1") (pintype "passive"))
    )
    (net (code "62") (name "Net-(LED15-Pad2)") (class "Default")
      (node (ref "LED15") (pin "2") (pinfunction "2_2") (pintype "passive"))
      (node (ref "R43") (pin "1") (pinfunction "1_1") (pintype "passive"))
    )
    (net (code "63") (name "Net-(LED16-Pad2)") (class "Default")
      (node (ref "LED16") (pin "2") (pinfunction "2_2") (pintype "passive"))
      (node (ref "R52") (pin "1") (pinfunction "1_1") (pintype "passive"))
    )
    (net (code "64") (name "Net-(LED17-Pad2)") (class "Default")
      (node (ref "LED17") (pin "2") (pinfunction "2_2") (pintype "passive"))
      (node (ref "R54") (pin "1") (pinfunction "1_1") (pintype "passive"))
    )
    (net (code "65") (name "Net-(LED18-Pad2)") (class "Default")
      (node (ref "LED18") (pin "2") (pinfunction "2_2") (pintype "passive"))
      (node (ref "R56") (pin "1") (pinfunction "1_1") (pintype "passive"))
    )
    (net (code "66") (name "Net-(LED19-Pad2)") (class "Default")
      (node (ref "LED19") (pin "2") (pinfunction "2_2") (pintype "passive"))
      (node (ref "R60") (pin "1") (pinfunction "1_1") (pintype "passive"))
    )
    (net (code "67") (name "Net-(U3-A)") (class "Default")
      (node (ref "R3") (pin "2") (pinfunction "2_2") (pintype "passive"))
      (node (ref "U3") (pin "1") (pinfunction "A_1") (pintype "passive"))
    )
    (net (code "68") (name "Net-(U4-A)") (class "Default")
      (node (ref "R6") (pin "2") (pinfunction "2_2") (pintype "passive"))
      (node (ref "U4") (pin "1") (pinfunction "A_1") (pintype "passive"))
    )
    (net (code "69") (name "Net-(U5-A)") (class "Default")
      (node (ref "R9") (pin "2") (pinfunction "2_2") (pintype "passive"))
      (node (ref "U5") (pin "1") (pinfunction "A_1") (pintype "passive"))
    )
    (net (code "70") (name "Net-(U6-A)") (class "Default")
      (node (ref "R16") (pin "2") (pinfunction "2_2") (pintype "passive"))
      (node (ref "U6") (pin "1") (pinfunction "A_1") (pintype "passive"))
    )
    (net (code "71") (name "Net-(U7-A)") (class "Default")
      (node (ref "R17") (pin "2") (pinfunction "2_2") (pintype "passive"))
      (node (ref "U7") (pin "1") (pinfunction "A_1") (pintype "passive"))
    )
    (net (code "72") (name "Net-(U8-A)") (class "Default")
      (node (ref "R21") (pin "2") (pinfunction "2_2") (pintype "passive"))
      (node (ref "U8") (pin "1") (pinfunction "A_1") (pintype "passive"))
    )
    (net (code "73") (name "Net-(U9-A)") (class "Default")
      (node (ref "R27") (pin "2") (pinfunction "2_2") (pintype "passive"))
      (node (ref "U9") (pin "1") (pinfunction "A_1") (pintype "passive"))
    )
    (net (code "74") (name "Net-(U10-A)") (class "Default")
      (node (ref "R29") (pin "2") (pinfunction "2_2") (pintype "passive"))
      (node (ref "U10") (pin "1") (pinfunction "A_1") (pintype "passive"))
    )
    (net (code "75") (name "Net-(U11-A)") (class "Default")
      (node (ref "R33") (pin "2") (pinfunction "2_2") (pintype "passive"))
      (node (ref "U11") (pin "1") (pinfunction "A_1") (pintype "passive"))
    )
    (net (code "76") (name "Net-(U12-A)") (class "Default")
      (node (ref "R39") (pin "2") (pinfunction "2_2") (pintype "passive"))
      (node (ref "U12") (pin "1") (pinfunction "A_1") (pintype "passive"))
    )
    (net (code "77") (name "Net-(U13-A)") (class "Default")
      (node (ref "R40") (pin "2") (pinfunction "2_2") (pintype "passive"))
      (node (ref "U13") (pin "1") (pinfunction "A_1") (pintype "passive"))
    )
    (net (code "78") (name "Net-(U14-A)") (class "Default")
      (node (ref "R49") (pin "2") (pinfunction "2_2") (pintype "passive"))
      (node (ref "U14") (pin "1") (pinfunction "A_1") (pintype "passive"))
    )
    (net (code "79") (name "Net-(U15-A)") (class "Default")
      (node (ref "R51") (pin "2") (pinfunction "2_2") (pintype "passive"))
      (node (ref "U15") (pin "1") (pinfunction "A_1") (pintype "passive"))
    )
    (net (code "80") (name "Net-(U16-A)") (class "Default")
      (node (ref "R59") (pin "2") (pinfunction "2_2") (pintype "passive"))
      (node (ref "U16") (pin "1") (pinfunction "A_1") (pintype "passive"))
    )
  )
)
